# Commutator.net
KiCad netlist of a schematic drawn in Altium Designer
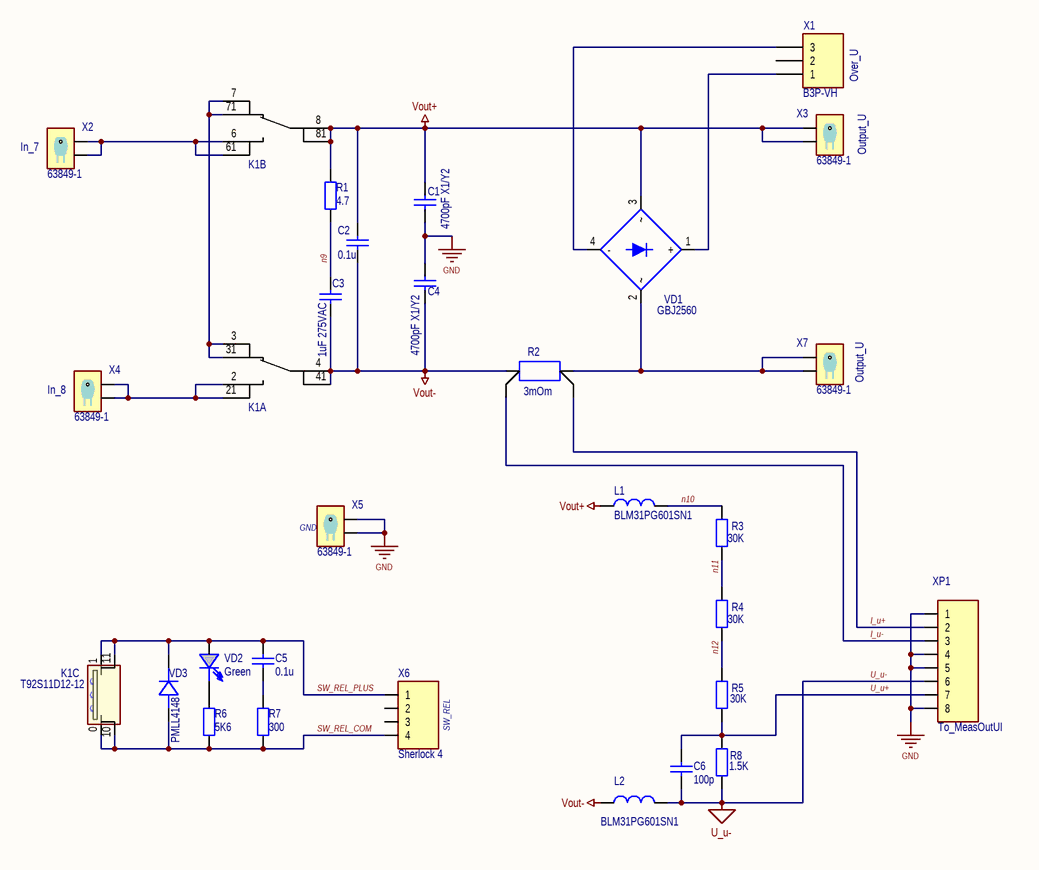
[diagram p0: Commutator.SchDoc]

(export (version "E")
  (design (tool "Eeschema 10.0.6"))
  (components
    (comp (ref "C1")
      (value "4700pF X1/Y2")
      (footprint "mainLib:SMD_C_2220")
      (description "SMD C2220 MURATA 250Vac 10% X7R X1Y2")
      (fields (field (name "PARTNUMBER") "GA355DR7GF472kW01") (field (name "MANUFACTURER") "MURATA"))
      (libsource (lib "mainRCLib") (part "C X1Y2 4700pF SMD 2220 250Vac 10%"))
    )
    (comp (ref "C2")
      (value "0.1u")
      (footprint "mainLib:SMD_C_1812")
      (description "SMD C 1812 MURATA 630V 10% X7R")
      (fields (field (name "PARTNUMBER") "GRM43DR72J104K") (field (name "MANUFACTURER") "MURATA"))
      (libsource (lib "mainRCLib") (part "C1812 0.1u 630V 10%"))
    )
    (comp (ref "C3")
      (value "1uF 275VAC")
      (footprint "mainLib:MKP_W13_H24_L31.5_LS27.5")
      (description "Polypropelene MKP-X2 L31.5 H24 W13 LS27.5")
      (fields (field (name "PARTNUMBER") "MKX21W41006D00M") (field (name "MANUFACTURER") "Wima"))
      (libsource (lib "mainRCLib") (part "MKP-X2 1uF 275VAC +-20% L31.5 H24 W13 LS27.5"))
    )
    (comp (ref "C4")
      (value "4700pF X1/Y2")
      (footprint "mainLib:SMD_C_2220")
      (description "SMD C2220 MURATA 250Vac 10% X7R X1Y2")
      (fields (field (name "PARTNUMBER") "GA355DR7GF472kW01") (field (name "MANUFACTURER") "MURATA"))
      (libsource (lib "mainRCLib") (part "C X1Y2 4700pF SMD 2220 250Vac 10%"))
    )
    (comp (ref "C5")
      (value "0.1u")
      (footprint "mainLib:SMD_C_0603")
      (description "SMD C 0603 MURATA 50V 10% X7R")
      (fields (field (name "PARTNUMBER") "GRM188R71H104K") (field (name "MANUFACTURER") "MURATA"))
      (libsource (lib "mainRCLib") (part "C0603 0.1u 50V 10%"))
    )
    (comp (ref "C6")
      (value "100p")
      (footprint "mainLib:SMD_C_0603")
      (description "SMD C 0603 MURATA 100V 5% NP0")
      (fields (field (name "PARTNUMBER") "GRM1885C2A101JA01") (field (name "MANUFACTURER") "MURATA"))
      (libsource (lib "mainRCLib") (part "C0603 100p 100V 5%"))
    )
    (comp (ref "K1")
      (value "T92S11D12-12")
      (footprint "mainLib:T92S11")
      (description "400VAC 30A DPDT 12VDC")
      (fields (field (name "PARTNUMBER") "1-1393212-0") (field (name "MANUFACTURER") "TE Connectivity"))
      (libsource (lib "") (part "T92S11D12-12_1"))
    )
    (comp (ref "L1")
      (value "BLM31PG601SN1")
      (footprint "mainLib:SMD_L_1206")
      (description "600R 1.5A (100MHz)")
      (fields (field (name "MANUFACTURER") "TDK"))
      (libsource (lib "mainLib") (part "BLM31PG601SN1"))
    )
    (comp (ref "L2")
      (value "BLM31PG601SN1")
      (footprint "mainLib:SMD_L_1206")
      (description "600R 1.5A (100MHz)")
      (fields (field (name "MANUFACTURER") "TDK"))
      (libsource (lib "mainLib") (part "BLM31PG601SN1"))
    )
    (comp (ref "R1")
      (value "4.7")
      (footprint "mainLib:PRW 5W 1050")
      (description "Выводной PRW 5W 4R7 +-5%")
      (fields (field (name "PARTNUMBER") "PRW05WJW47J") (field (name "MANUFACTURER") "RoyalOhm"))
      (libsource (lib "mainRCLib") (part "PRW 4.7 5W +-5%"))
    )
    (comp (ref "R2")
      (value "3mOm")
      (footprint "mainLib:WSL3637 3mOm")
      (description "WSL3637 1mOm 3W 1% 50ppm")
      (fields (field (name "PARTNUMBER") "WSL36373L000F") (field (name "MANUFACTURER") "Vishay"))
      (libsource (lib "mainLib") (part "WSL3637 3mOm 3W"))
    )
    (comp (ref "R3")
      (value "30K")
      (footprint "mainLib:SMD_R_1206")
      (description "SMD R 1206 VISHAY 0.25W 2000V 0.1% 25ppm")
      (fields (field (name "PARTNUMBER") "TNPW120630K0BE") (field (name "MANUFACTURER") "VISHAY"))
      (libsource (lib "mainRCLib") (part "R1206 30K 0.1%"))
    )
    (comp (ref "R4")
      (value "30K")
      (footprint "mainLib:SMD_R_1206")
      (description "SMD R 1206 VISHAY 0.25W 2000V 0.1% 25ppm")
      (fields (field (name "PARTNUMBER") "TNPW120630K0BE") (field (name "MANUFACTURER") "VISHAY"))
      (libsource (lib "mainRCLib") (part "R1206 30K 0.1%"))
    )
    (comp (ref "R5")
      (value "30K")
      (footprint "mainLib:SMD_R_1206")
      (description "SMD R 1206 VISHAY 0.25W 2000V 0.1% 25ppm")
      (fields (field (name "PARTNUMBER") "TNPW120630K0BE") (field (name "MANUFACTURER") "VISHAY"))
      (libsource (lib "mainRCLib") (part "R1206 30K 0.1%"))
    )
    (comp (ref "R6")
      (value "5K6")
      (footprint "mainLib:SMD_R_0603")
      (description "SMD R 0603 VISHAY 0.1W 75V 1% 100ppm")
      (fields (field (name "PARTNUMBER") "CRCW06035K60FK") (field (name "MANUFACTURER") "VISHAY"))
      (libsource (lib "mainRCLib") (part "R0603 5K6 1%"))
    )
    (comp (ref "R7")
      (value "300")
      (footprint "mainLib:SMD_R_0805")
      (description "SMD R 0805 VISHAY 0.125W 150V 1% 100ppm")
      (fields (field (name "PARTNUMBER") "CRCW0805300RFK") (field (name "MANUFACTURER") "VISHAY"))
      (libsource (lib "mainRCLib") (part "R0805 300 1%"))
    )
    (comp (ref "R8")
      (value "1.5K")
      (footprint "mainLib:SMD_R_0805")
      (description "SMD R 0805 VISHAY 0.125W 150V 0.1% 25ppm")
      (fields (field (name "PARTNUMBER") "TNPW08051K50BE") (field (name "MANUFACTURER") "VISHAY"))
      (libsource (lib "mainRCLib") (part "R0805 1.5K 0.1%"))
    )
    (comp (ref "VD1")
      (value "GBJ2560")
      (footprint "mainLib:GSIB-5S")
      (description "25A 600V")
      (fields (field (name "MANUFACTURER") "Vishay") (field (name "PARTNUMBER") "GSIB2560-E3/45"))
      (libsource (lib "mainLib") (part "GBJ2560"))
    )
    (comp (ref "VD2")
      (value "Green")
      (footprint "mainLib:SMD_LED_LL_Green")
      (description "LED Green SMD")
      (fields (field (name "PARTNUMBER") "LL-S172GC-2A") (field (name "MANUFACTURER") "Lucky Light"))
      (libsource (lib "mainLib") (part "LL-S172GC-2A"))
    )
    (comp (ref "VD3")
      (value "PMLL4148")
      (footprint "mainLib:SOD80C")
      (description "If=0.2A, Vf=1V Vrrm=100V Diode (SOD80C)")
      (fields (field (name "MANUFACTURER") "NXP Semiconductors"))
      (libsource (lib "mainLib") (part "PMLL4148"))
    )
    (comp (ref "X1")
      (value "B3P-VH")
      (footprint "mainLib:B3P-VH")
      (description "VH Top, 10A 250V 3.96mm")
      (fields (field (name "MANUFACTURER") "JST"))
      (libsource (lib "mainLib") (part "B3P-VH"))
    )
    (comp (ref "X2")
      (value "63849-1")
      (footprint "63849-1+insulator(154719-1)")
      (description "PCB, 6.3х0.8, hole")
      (fields (field (name "MANUFACTURER") "TE Connectivity"))
      (libsource (lib "") (part "63849-1_1"))
    )
    (comp (ref "X3")
      (value "63849-1")
      (footprint "63849-1+insulator(154719-1)")
      (description "PCB, 6.3х0.8, hole")
      (fields (field (name "MANUFACTURER") "TE Connectivity"))
      (libsource (lib "mainLib") (part "63849-1"))
    )
    (comp (ref "X4")
      (value "63849-1")
      (footprint "63849-1+insulator(154719-1)")
      (description "PCB, 6.3х0.8, hole")
      (fields (field (name "MANUFACTURER") "TE Connectivity"))
      (libsource (lib "") (part "63849-1_1"))
    )
    (comp (ref "X5")
      (value "63849-1")
      (footprint "63849-1+insulator(154719-1)")
      (description "PCB, 6.3х0.8, hole")
      (fields (field (name "MANUFACTURER") "TE Connectivity"))
      (libsource (lib "") (part "63849-1_1"))
    )
    (comp (ref "X6")
      (value "Sherlock 4")
      (footprint "35362-0450")
      (description "Sherlock 4 Top, 2A 125V 2mm")
      (fields (field (name "PARTNUMBER") "35362-0450") (field (name "MANUFACTURER") "MOLEX"))
      (libsource (lib "mainLib") (part "35362-0450"))
    )
    (comp (ref "X7")
      (value "63849-1")
      (footprint "63849-1+insulator(154719-1)")
      (description "PCB, 6.3х0.8, hole")
      (fields (field (name "MANUFACTURER") "TE Connectivity"))
      (libsource (lib "mainLib") (part "63849-1"))
    )
    (comp (ref "XP1")
      (value "То_MeasOutUI")
      (footprint "mainLib:XP(MeasOutUIBoard)")
      (description "to MeasOutUI")
      (fields (field (name "PARTNUMBER") "R100.230.080.000") (field (name "MANUFACTURER") "OLTEST"))
      (libsource (lib "mainLib") (part "Plata_MeasOutUI"))
    )
  )
  (nets
    (net (code "1") (name "/I_u+") (class "Default")
      (node (ref "R2") (pin "2") (pinfunction "E1_2") (pintype "passive"))
      (node (ref "XP1") (pin "2") (pinfunction "2_2") (pintype "passive"))
    )
    (net (code "2") (name "/I_u-") (class "Default")
      (node (ref "R2") (pin "4") (pinfunction "E2_4") (pintype "passive"))
      (node (ref "XP1") (pin "3") (pinfunction "3_3") (pintype "passive"))
    )
    (net (code "3") (name "/SW_REL_COM") (class "Default")
      (node (ref "K1") (pin "0") (pinfunction "0_0") (pintype "passive"))
      (node (ref "K1") (pin "10") (pinfunction "10_10") (pintype "passive"))
      (node (ref "R6") (pin "1") (pinfunction "1_1") (pintype "passive"))
      (node (ref "R7") (pin "1") (pinfunction "1_1") (pintype "passive"))
      (node (ref "VD3") (pin "1") (pinfunction "ANODE_1") (pintype "passive"))
      (node (ref "X6") (pin "4") (pinfunction "4_4") (pintype "passive"))
    )
    (net (code "4") (name "/SW_REL_PLUS") (class "Default")
      (node (ref "C5") (pin "2") (pinfunction "2_2") (pintype "passive"))
      (node (ref "K1") (pin "1") (pinfunction "1_1") (pintype "passive"))
      (node (ref "K1") (pin "11") (pinfunction "11_11") (pintype "passive"))
      (node (ref "VD2") (pin "1") (pinfunction "ANODE_1") (pintype "passive"))
      (node (ref "VD3") (pin "2") (pinfunction "CATHODE_2") (pintype "passive"))
      (node (ref "X6") (pin "1") (pinfunction "1_1") (pintype "passive"))
    )
    (net (code "5") (name "/U_u+") (class "Default")
      (node (ref "C6") (pin "2") (pinfunction "2_2") (pintype "passive"))
      (node (ref "R5") (pin "1") (pinfunction "1_1") (pintype "passive"))
      (node (ref "R8") (pin "2") (pinfunction "2_2") (pintype "passive"))
      (node (ref "XP1") (pin "7") (pinfunction "7_7") (pintype "passive"))
    )
    (net (code "6") (name "/n9") (class "Default")
      (node (ref "C3") (pin "2") (pinfunction "2_2") (pintype "passive"))
      (node (ref "R1") (pin "1") (pinfunction "1_1") (pintype "passive"))
    )
    (net (code "7") (name "/n10") (class "Default")
      (node (ref "L1") (pin "2") (pinfunction "2_2") (pintype "passive"))
      (node (ref "R3") (pin "2") (pinfunction "2_2") (pintype "passive"))
    )
    (net (code "8") (name "/n11") (class "Default")
      (node (ref "R3") (pin "1") (pinfunction "1_1") (pintype "passive"))
      (node (ref "R4") (pin "2") (pinfunction "2_2") (pintype "passive"))
    )
    (net (code "9") (name "/n12") (class "Default")
      (node (ref "R4") (pin "1") (pinfunction "1_1") (pintype "passive"))
      (node (ref "R5") (pin "2") (pinfunction "2_2") (pintype "passive"))
    )
    (net (code "10") (name "GND") (class "Default")
      (node (ref "C1") (pin "1") (pinfunction "1_1") (pintype "passive"))
      (node (ref "C4") (pin "2") (pinfunction "2_2") (pintype "passive"))
      (node (ref "X5") (pin "1") (pinfunction "1_1") (pintype "passive"))
      (node (ref "X5") (pin "2") (pinfunction "2_2") (pintype "passive"))
      (node (ref "XP1") (pin "1") (pinfunction "1_1") (pintype "passive"))
      (node (ref "XP1") (pin "4") (pinfunction "4_4") (pintype "passive"))
      (node (ref "XP1") (pin "5") (pinfunction "5_5") (pintype "passive"))
      (node (ref "XP1") (pin "8") (pinfunction "8_8") (pintype "passive"))
    )
    (net (code "11") (name "Net-(C5-Pad1)") (class "Default")
      (node (ref "C5") (pin "1") (pinfunction "1_1") (pintype "passive"))
      (node (ref "R7") (pin "2") (pinfunction "2_2") (pintype "passive"))
    )
    (net (code "12") (name "Net-(K1-Pad2)") (class "Default")
      (node (ref "K1") (pin "2") (pinfunction "2_2") (pintype "passive"))
      (node (ref "K1") (pin "21") (pinfunction "21_21") (pintype "passive"))
      (node (ref "X4") (pin "1") (pinfunction "1_1") (pintype "passive"))
      (node (ref "X4") (pin "2") (pinfunction "2_2") (pintype "passive"))
    )
    (net (code "13") (name "Net-(K1-Pad3)") (class "Default")
      (node (ref "K1") (pin "3") (pinfunction "3_3") (pintype "passive"))
      (node (ref "K1") (pin "31") (pinfunction "31_31") (pintype "passive"))
      (node (ref "K1") (pin "7") (pinfunction "7_7") (pintype "passive"))
      (node (ref "K1") (pin "71") (pinfunction "71_71") (pintype "passive"))
    )
    (net (code "14") (name "Net-(K1-Pad6)") (class "Default")
      (node (ref "K1") (pin "6") (pinfunction "6_6") (pintype "passive"))
      (node (ref "K1") (pin "61") (pinfunction "61_61") (pintype "passive"))
      (node (ref "X2") (pin "1") (pinfunction "1_1") (pintype "passive"))
      (node (ref "X2") (pin "2") (pinfunction "2_2") (pintype "passive"))
    )
    (net (code "15") (name "Net-(R2-I1)") (class "Default")
      (node (ref "R2") (pin "1") (pinfunction "I1_1") (pintype "passive"))
      (node (ref "VD1") (pin "2") (pinfunction "~_2") (pintype "passive"))
      (node (ref "X7") (pin "1") (pinfunction "1_1") (pintype "passive"))
      (node (ref "X7") (pin "2") (pinfunction "2_2") (pintype "passive"))
    )
    (net (code "16") (name "Net-(VD1-+)") (class "Default")
      (node (ref "VD1") (pin "1") (pinfunction "+_1") (pintype "passive"))
      (node (ref "X1") (pin "1") (pinfunction "1_1") (pintype "passive"))
    )
    (net (code "17") (name "Net-(VD1--)") (class "Default")
      (node (ref "VD1") (pin "4") (pinfunction "-_4") (pintype "passive"))
      (node (ref "X1") (pin "3") (pinfunction "3_3") (pintype "passive"))
    )
    (net (code "18") (name "Net-(VD2-CATHODE)") (class "Default")
      (node (ref "R6") (pin "2") (pinfunction "2_2") (pintype "passive"))
      (node (ref "VD2") (pin "2") (pinfunction "CATHODE_2") (pintype "passive"))
    )
    (net (code "19") (name "U_u-") (class "Default")
      (node (ref "C6") (pin "1") (pinfunction "1_1") (pintype "passive"))
      (node (ref "L2") (pin "2") (pinfunction "2_2") (pintype "passive"))
      (node (ref "R8") (pin "1") (pinfunction "1_1") (pintype "passive"))
      (node (ref "XP1") (pin "6") (pinfunction "6_6") (pintype "passive"))
    )
    (net (code "20") (name "Vout+") (class "Default")
      (node (ref "C1") (pin "2") (pinfunction "2_2") (pintype "passive"))
      (node (ref "C2") (pin "1") (pinfunction "1_1") (pintype "passive"))
      (node (ref "K1") (pin "8") (pinfunction "8_8") (pintype "passive"))
      (node (ref "K1") (pin "81") (pinfunction "81_81") (pintype "passive"))
      (node (ref "L1") (pin "1") (pinfunction "1_1") (pintype "passive"))
      (node (ref "R1") (pin "2") (pinfunction "2_2") (pintype "passive"))
      (node (ref "VD1") (pin "3") (pinfunction "~_3") (pintype "passive"))
      (node (ref "X3") (pin "1") (pinfunction "1_1") (pintype "passive"))
      (node (ref "X3") (pin "2") (pinfunction "2_2") (pintype "passive"))
    )
    (net (code "21") (name "Vout-") (class "Default")
      (node (ref "C2") (pin "2") (pinfunction "2_2") (pintype "passive"))
      (node (ref "C3") (pin "1") (pinfunction "1_1") (pintype "passive"))
      (node (ref "C4") (pin "1") (pinfunction "1_1") (pintype "passive"))
      (node (ref "K1") (pin "4") (pinfunction "4_4") (pintype "passive"))
      (node (ref "K1") (pin "41") (pinfunction "41_41") (pintype "passive"))
      (node (ref "L2") (pin "1") (pinfunction "1_1") (pintype "passive"))
      (node (ref "R2") (pin "3") (pinfunction "I2_3") (pintype "passive"))
    )
    (net (code "22") (name "unconnected-(X1-Pad2)") (class "Default")
      (node (ref "X1") (pin "2") (pinfunction "2_2") (pintype "passive"))
    )
    (net (code "23") (name "unconnected-(X6-Pad2)") (class "Default")
      (node (ref "X6") (pin "2") (pinfunction "2_2") (pintype "passive"))
    )
    (net (code "24") (name "unconnected-(X6-Pad3)") (class "Default")
      (node (ref "X6") (pin "3") (pinfunction "3_3") (pintype "passive"))
    )
  )
)
